# 2_MCU_schdoc.net
KiCad netlist of a schematic drawn in Altium Designer
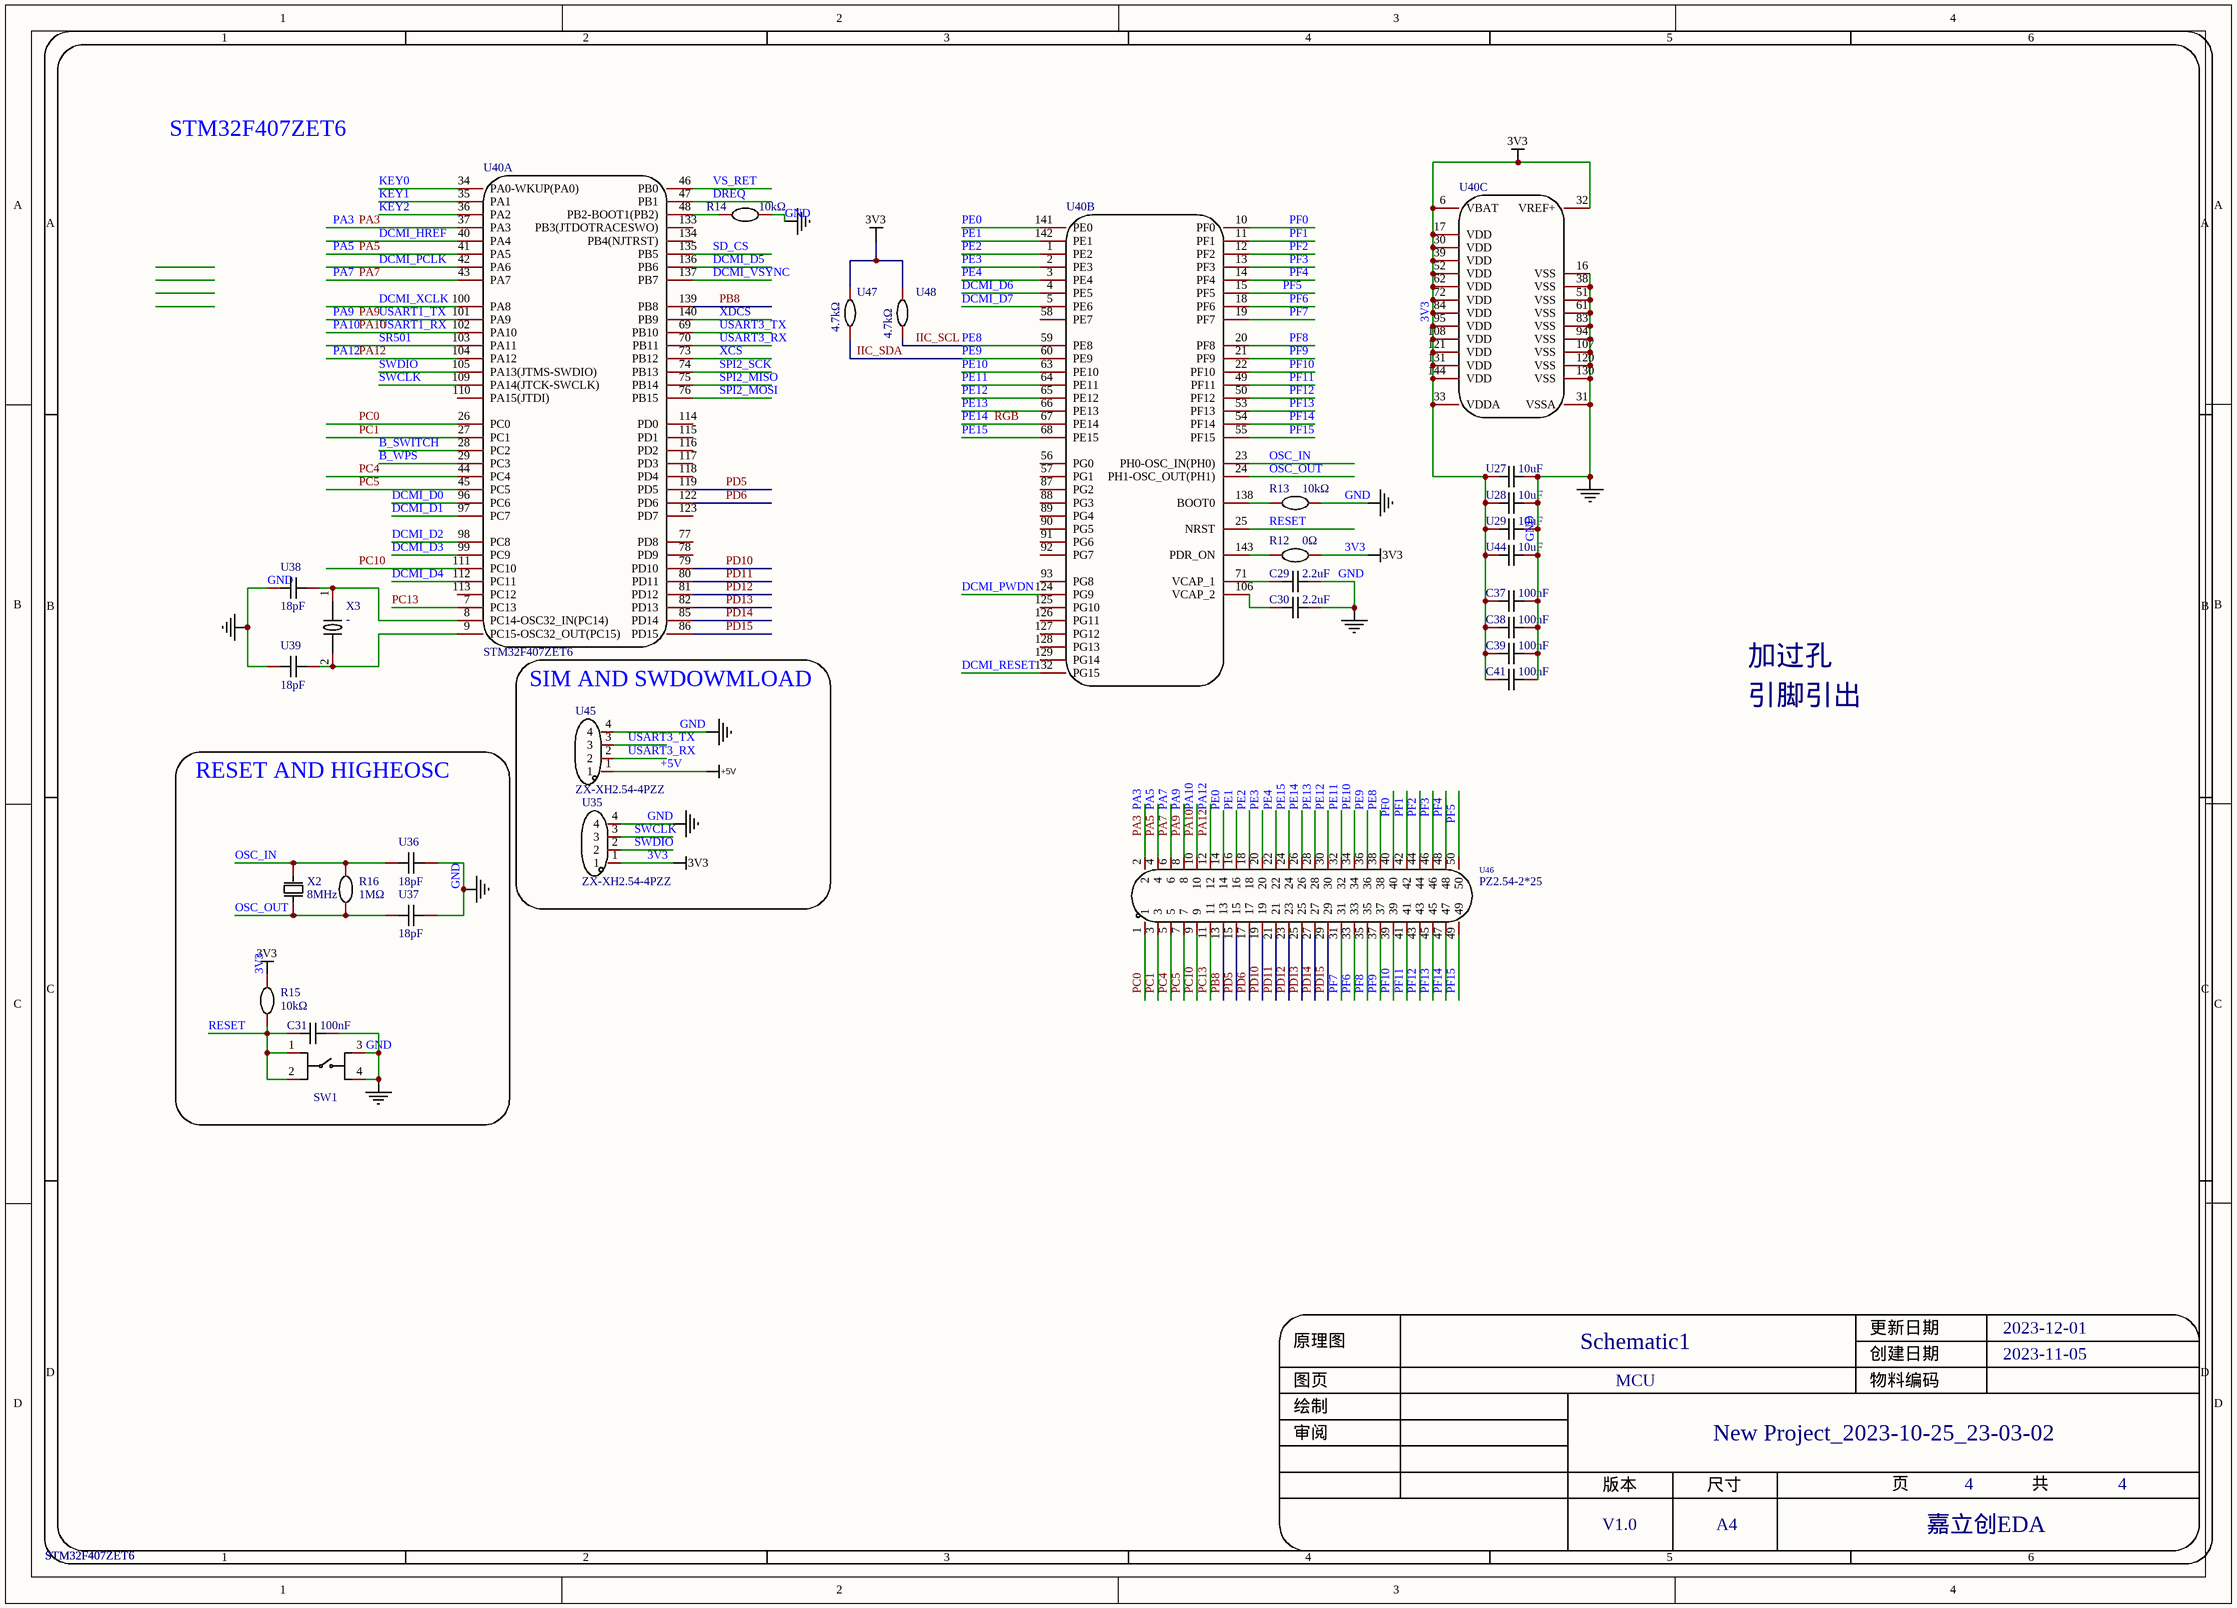
[diagram p0: 2_MCU.schdoc.schdoc]

(export (version "E")
  (design (tool "Eeschema 10.0.6"))
  (components
    (comp (ref "C29")
      (value "2.2uF")
      (footprint "C0603")
      (description "容值:2.2uF;精度:±10%;额定电压:10V;材质(温度系数):X6S;")
      (fields
        (field (name "NAME") "2.2uF")
        (field (name "MANUFACTURER") "TDK")
        (field (name "MANUFACTURER PART") "C1608X6S1A225K080AB")
      )
      (libsource (lib "altium-import") (part "root_0_C1608X6S1A225K080AB_"))
    )
    (comp (ref "C30")
      (value "2.2uF")
      (footprint "C0603")
      (description "容值:2.2uF;精度:±10%;额定电压:10V;材质(温度系数):X6S;")
      (fields
        (field (name "NAME") "2.2uF")
        (field (name "MANUFACTURER") "TDK")
        (field (name "MANUFACTURER PART") "C1608X6S1A225K080AB")
      )
      (libsource (lib "altium-import") (part "root_0_C1608X6S1A225K080AB_"))
    )
    (comp (ref "C31")
      (value "100nF")
      (footprint "C0603")
      (description "容值:100nF;精度:±20%;额定电压:50V;材质(温度系数):X8R;")
      (fields
        (field (name "NAME") "100nF")
        (field (name "MANUFACTURER") "TDK")
        (field (name "MANUFACTURER PART") "CGA3E3X8R1H104M080AE")
      )
      (libsource (lib "altium-import") (part "root_0_CGA3E3X8R1H104M080AE_"))
    )
    (comp (ref "C37")
      (value "100nF")
      (footprint "C0603")
      (description "容值:100nF;精度:±20%;额定电压:50V;材质(温度系数):X8R;")
      (fields
        (field (name "NAME") "100nF")
        (field (name "MANUFACTURER") "TDK")
        (field (name "MANUFACTURER PART") "CGA3E3X8R1H104M080AE")
      )
      (libsource (lib "altium-import") (part "root_0_CGA3E3X8R1H104M080AE_"))
    )
    (comp (ref "C38")
      (value "100nF")
      (footprint "C0603")
      (description "容值:100nF;精度:±20%;额定电压:50V;材质(温度系数):X8R;")
      (fields
        (field (name "NAME") "100nF")
        (field (name "MANUFACTURER") "TDK")
        (field (name "MANUFACTURER PART") "CGA3E3X8R1H104M080AE")
      )
      (libsource (lib "altium-import") (part "root_0_CGA3E3X8R1H104M080AE_"))
    )
    (comp (ref "C39")
      (value "100nF")
      (footprint "C0603")
      (description "容值:100nF;精度:±20%;额定电压:50V;材质(温度系数):X8R;")
      (fields
        (field (name "NAME") "100nF")
        (field (name "MANUFACTURER") "TDK")
        (field (name "MANUFACTURER PART") "CGA3E3X8R1H104M080AE")
      )
      (libsource (lib "altium-import") (part "root_0_CGA3E3X8R1H104M080AE_"))
    )
    (comp (ref "C41")
      (value "100nF")
      (footprint "C0603")
      (description "容值:100nF;精度:±20%;额定电压:50V;材质(温度系数):X8R;")
      (fields
        (field (name "NAME") "100nF")
        (field (name "MANUFACTURER") "TDK")
        (field (name "MANUFACTURER PART") "CGA3E3X8R1H104M080AE")
      )
      (libsource (lib "altium-import") (part "root_0_CGA3E3X8R1H104M080AE_"))
    )
    (comp (ref "R12")
      (value "0Ω")
      (footprint "R0603")
      (description "电阻类型:厚膜电阻;阻值:0Ω;精度:-;功率:100mW;")
      (fields
        (field (name "NAME") "0Ω")
        (field (name "MANUFACTURER") "YAGEO(国巨)")
        (field (name "MANUFACTURER PART") "RC0603JR-130RL")
      )
      (libsource (lib "altium-import") (part "root_0_RC0603JR-130RL_"))
    )
    (comp (ref "R13")
      (value "10kΩ")
      (footprint "R0603")
      (description "阻值:10kΩ;精度:±5%;")
      (fields
        (field (name "NAME") "10kΩ")
        (field (name "MANUFACTURER") "VO(翔胜)")
        (field (name "MANUFACTURER PART") "SCR0603J10K")
      )
      (libsource (lib "altium-import") (part "root_0_SCR0603J10K_"))
    )
    (comp (ref "R14")
      (value "10kΩ")
      (footprint "R0603")
      (description "阻值:10kΩ;精度:±5%;")
      (fields
        (field (name "NAME") "10kΩ")
        (field (name "MANUFACTURER") "VO(翔胜)")
        (field (name "MANUFACTURER PART") "SCR0603J10K")
      )
      (libsource (lib "altium-import") (part "root_0_SCR0603J10K_"))
    )
    (comp (ref "R15")
      (value "10kΩ")
      (footprint "R0603")
      (description "阻值:10kΩ;精度:±5%;")
      (fields
        (field (name "NAME") "10kΩ")
        (field (name "MANUFACTURER") "VO(翔胜)")
        (field (name "MANUFACTURER PART") "SCR0603J10K")
      )
      (libsource (lib "altium-import") (part "root_1_SCR0603J10K_"))
    )
    (comp (ref "R16")
      (value "1MΩ")
      (footprint "R0603")
      (description "电阻类型:厚膜电阻;阻值:1MΩ;精度:±5%;功率:100mW;")
      (fields
        (field (name "NAME") "1MΩ")
        (field (name "MANUFACTURER") "VISHAY(威世)")
        (field (name "MANUFACTURER PART") "CRCW06031M00JNEAC")
      )
      (libsource (lib "altium-import") (part "root_1_CRCW06031M00JNEAC_"))
    )
    (comp (ref "SW1")
      (value "K2-6639SP-C4SC-04")
      (footprint "KEY-SMD_4P-L6.0-W6.0-P3.90-LS10.0")
      (fields (field (name "MANUFACTURER") "韩国韩荣"))
      (libsource (lib "altium-import") (part "root_0_K2-6639SP-C4SC-04_"))
    )
    (comp (ref "U27")
      (value "10uF")
      (footprint "C0603")
      (description "容值:10uF;精度:±20%;额定电压:16V;材质(温度系数):JB;")
      (fields
        (field (name "NAME") "10uF")
        (field (name "MANUFACTURER") "TDK")
        (field (name "MANUFACTURER PART") "C1608JB1C106M080AB")
      )
      (libsource (lib "altium-import") (part "root_0_C1608JB1C106M080AB_"))
    )
    (comp (ref "U28")
      (value "10uF")
      (footprint "C0603")
      (description "容值:10uF;精度:±20%;额定电压:16V;材质(温度系数):JB;")
      (fields
        (field (name "NAME") "10uF")
        (field (name "MANUFACTURER") "TDK")
        (field (name "MANUFACTURER PART") "C1608JB1C106M080AB")
      )
      (libsource (lib "altium-import") (part "root_0_C1608JB1C106M080AB_"))
    )
    (comp (ref "U29")
      (value "10uF")
      (footprint "C0603")
      (description "容值:10uF;精度:±20%;额定电压:16V;材质(温度系数):JB;")
      (fields
        (field (name "NAME") "10uF")
        (field (name "MANUFACTURER") "TDK")
        (field (name "MANUFACTURER PART") "C1608JB1C106M080AB")
      )
      (libsource (lib "altium-import") (part "root_0_C1608JB1C106M080AB_"))
    )
    (comp (ref "U35")
      (value "ZX-XH2.54-4PZZ")
      (footprint "CONN-TH_4P-P2.50_4PIN")
      (fields (field (name "NAME") "ZX-XH2.54-4PZZ") (field (name "MANUFACTURER") "Megastar(兆星)"))
      (libsource (lib "altium-import") (part "root_2_ZX-XH2.54-4PZZ_"))
    )
    (comp (ref "U36")
      (value "18pF")
      (footprint "C0603")
      (description "容值:18pF;精度:±5%;额定电压:100V;材质(温度系数):CH;")
      (fields
        (field (name "NAME") "18pF")
        (field (name "MANUFACTURER") "TDK")
        (field (name "MANUFACTURER PART") "C1608CH2A180J080AA")
      )
      (libsource (lib "altium-import") (part "root_0_C1608CH2A180J080AA_"))
    )
    (comp (ref "U37")
      (value "18pF")
      (footprint "C0603")
      (description "容值:18pF;精度:±5%;额定电压:100V;材质(温度系数):CH;")
      (fields
        (field (name "NAME") "18pF")
        (field (name "MANUFACTURER") "TDK")
        (field (name "MANUFACTURER PART") "C1608CH2A180J080AA")
      )
      (libsource (lib "altium-import") (part "root_0_C1608CH2A180J080AA_"))
    )
    (comp (ref "U38")
      (value "18pF")
      (footprint "C0603")
      (description "容值:18pF;精度:±5%;额定电压:100V;材质(温度系数):CH;")
      (fields
        (field (name "NAME") "18pF")
        (field (name "MANUFACTURER") "TDK")
        (field (name "MANUFACTURER PART") "C1608CH2A180J080AA")
      )
      (libsource (lib "altium-import") (part "root_0_C1608CH2A180J080AA_"))
    )
    (comp (ref "U39")
      (value "18pF")
      (footprint "C0603")
      (description "容值:18pF;精度:±5%;额定电压:100V;材质(温度系数):CH;")
      (fields
        (field (name "NAME") "18pF")
        (field (name "MANUFACTURER") "TDK")
        (field (name "MANUFACTURER PART") "C1608CH2A180J080AA")
      )
      (libsource (lib "altium-import") (part "root_0_C1608CH2A180J080AA_"))
    )
    (comp (ref "U40")
      (value "STM32F407ZET6")
      (footprint "LQFP-144_L20.0-W20.0-P0.50-LS22.0-BL")
      (fields (field (name "NAME") "STM32F407ZET6") (field (name "MANUFACTURER") "ST(意法半导体)"))
      (libsource (lib "altium-import") (part "root_0_STM32F407ZET6_"))
    )
    (comp (ref "U44")
      (value "10uF")
      (footprint "C0603")
      (description "容值:10uF;精度:±20%;额定电压:16V;材质(温度系数):JB;")
      (fields
        (field (name "NAME") "10uF")
        (field (name "MANUFACTURER") "TDK")
        (field (name "MANUFACTURER PART") "C1608JB1C106M080AB")
      )
      (libsource (lib "altium-import") (part "root_0_C1608JB1C106M080AB_"))
    )
    (comp (ref "U45")
      (value "ZX-XH2.54-4PZZ")
      (footprint "CONN-TH_4P-P2.50_4PIN")
      (fields (field (name "NAME") "ZX-XH2.54-4PZZ") (field (name "MANUFACTURER") "Megastar(兆星)"))
      (libsource (lib "altium-import") (part "root_2_ZX-XH2.54-4PZZ_"))
    )
    (comp (ref "U46")
      (value "PZ2.54-2*25")
      (footprint "HDR-TH_50P-P2.54-V-M-R2-C25-S2.54")
      (fields (field (name "NAME") "PZ2.54-2*25") (field (name "MANUFACTURER") "ZHOURI(洲日)"))
      (libsource (lib "altium-import") (part "root_1_PZ2.54-2*25_"))
    )
    (comp (ref "U47")
      (value "4.7kΩ")
      (footprint "R0603")
      (description "电阻类型:薄膜电阻;阻值:4.7kΩ;精度:±1%;功率:100mW;")
      (fields
        (field (name "NAME") "4.7kΩ")
        (field (name "MANUFACTURER") "Viking(光颉)")
        (field (name "MANUFACTURER PART") "AR03FTDX4701A")
      )
      (libsource (lib "altium-import") (part "root_3_AR03FTDX4701A_"))
    )
    (comp (ref "U48")
      (value "4.7kΩ")
      (footprint "R0603")
      (description "电阻类型:薄膜电阻;阻值:4.7kΩ;精度:±1%;功率:100mW;")
      (fields
        (field (name "NAME") "4.7kΩ")
        (field (name "MANUFACTURER") "Viking(光颉)")
        (field (name "MANUFACTURER PART") "AR03FTDX4701A")
      )
      (libsource (lib "altium-import") (part "root_3_AR03FTDX4701A_"))
    )
    (comp (ref "X2")
      (value "8MHz")
      (footprint "OSC-SMD_L5.0-W3.2")
      (description "频率:8MHz;频率公差:±30ppm;负载电容:20pF;")
      (fields
        (field (name "NAME") "8MHz")
        (field (name "MANUFACTURER") "TAE(雅晶鑫)")
        (field (name "MANUFACTURER PART") "TAXM8M2QLFCDT1T")
      )
      (libsource (lib "altium-import") (part "root_1_TAXM8M2QLFCDT1T_"))
    )
    (comp (ref "X3")
      (value "-")
      (footprint "OSC-SMD_2P-L1.6-W1.0")
      (description "频率:-;负载电容:-;")
      (fields
        (field (name "NAME") "-")
        (field (name "MANUFACTURER") "RIVER(大河)")
        (field (name "MANUFACTURER PART") "TFX-04-32.768K")
      )
      (libsource (lib "altium-import") (part "root_3_TFX-04-32.768K_"))
    )
  )
  (nets
    (net (code "1") (name "+5V") (class "Default")
      (node (ref "U45") (pin "1") (pinfunction "1_1") (pintype "passive"))
    )
    (net (code "2") (name "/B_SWITCH") (class "Default")
      (node (ref "U40") (pin "28") (pinfunction "PC2_28") (pintype "passive"))
    )
    (net (code "3") (name "/B_WPS") (class "Default")
      (node (ref "U40") (pin "29") (pinfunction "PC3_29") (pintype "passive"))
    )
    (net (code "4") (name "/DCMI_D0") (class "Default")
      (node (ref "U40") (pin "96") (pinfunction "PC6_96") (pintype "passive"))
    )
    (net (code "5") (name "/DCMI_D1") (class "Default")
      (node (ref "U40") (pin "97") (pinfunction "PC7_97") (pintype "passive"))
    )
    (net (code "6") (name "/DCMI_D2") (class "Default")
      (node (ref "U40") (pin "98") (pinfunction "PC8_98") (pintype "passive"))
    )
    (net (code "7") (name "/DCMI_D3") (class "Default")
      (node (ref "U40") (pin "99") (pinfunction "PC9_99") (pintype "passive"))
    )
    (net (code "8") (name "/DCMI_D4") (class "Default")
      (node (ref "U40") (pin "112") (pinfunction "PC11_112") (pintype "passive"))
    )
    (net (code "9") (name "/DCMI_D5") (class "Default")
      (node (ref "U40") (pin "136") (pinfunction "PB6_136") (pintype "passive"))
    )
    (net (code "10") (name "/DCMI_D6") (class "Default")
      (node (ref "U40") (pin "4") (pinfunction "PE5_4") (pintype "passive"))
    )
    (net (code "11") (name "/DCMI_D7") (class "Default")
      (node (ref "U40") (pin "5") (pinfunction "PE6_5") (pintype "passive"))
    )
    (net (code "12") (name "/DCMI_HREF") (class "Default")
      (node (ref "U40") (pin "40") (pinfunction "PA4_40") (pintype "passive"))
    )
    (net (code "13") (name "/DCMI_PCLK") (class "Default")
      (node (ref "U40") (pin "42") (pinfunction "PA6_42") (pintype "passive"))
    )
    (net (code "14") (name "/DCMI_PWDN") (class "Default")
      (node (ref "U40") (pin "124") (pinfunction "PG9_124") (pintype "passive"))
    )
    (net (code "15") (name "/DCMI_RESET") (class "Default")
      (node (ref "U40") (pin "132") (pinfunction "PG15_132") (pintype "passive"))
    )
    (net (code "16") (name "/DCMI_VSYNC") (class "Default")
      (node (ref "U40") (pin "137") (pinfunction "PB7_137") (pintype "passive"))
    )
    (net (code "17") (name "/DCMI_XCLK") (class "Default")
      (node (ref "U40") (pin "100") (pinfunction "PA8_100") (pintype "passive"))
    )
    (net (code "18") (name "/DREQ") (class "Default")
      (node (ref "U40") (pin "47") (pinfunction "PB1_47") (pintype "passive"))
    )
    (net (code "19") (name "/GND") (class "Default")
      (node (ref "C29") (pin "2") (pinfunction "2_2") (pintype "passive"))
      (node (ref "C30") (pin "2") (pinfunction "2_2") (pintype "passive"))
      (node (ref "C31") (pin "2") (pinfunction "2_2") (pintype "passive"))
      (node (ref "C37") (pin "2") (pinfunction "2_2") (pintype "passive"))
      (node (ref "C38") (pin "2") (pinfunction "2_2") (pintype "passive"))
      (node (ref "C39") (pin "2") (pinfunction "2_2") (pintype "passive"))
      (node (ref "C41") (pin "2") (pinfunction "2_2") (pintype "passive"))
      (node (ref "R13") (pin "2") (pinfunction "2_2") (pintype "passive"))
      (node (ref "R14") (pin "2") (pinfunction "2_2") (pintype "passive"))
      (node (ref "SW1") (pin "3") (pinfunction "3_3") (pintype "passive"))
      (node (ref "SW1") (pin "4") (pinfunction "4_4") (pintype "passive"))
      (node (ref "U27") (pin "2") (pinfunction "2_2") (pintype "passive"))
      (node (ref "U28") (pin "2") (pinfunction "2_2") (pintype "passive"))
      (node (ref "U29") (pin "2") (pinfunction "2_2") (pintype "passive"))
      (node (ref "U35") (pin "4") (pinfunction "4_4") (pintype "passive"))
      (node (ref "U36") (pin "2") (pinfunction "2_2") (pintype "passive"))
      (node (ref "U37") (pin "2") (pinfunction "2_2") (pintype "passive"))
      (node (ref "U38") (pin "1") (pinfunction "1_1") (pintype "passive"))
      (node (ref "U39") (pin "1") (pinfunction "1_1") (pintype "passive"))
      (node (ref "U40") (pin "107") (pinfunction "VSS_107") (pintype "passive"))
      (node (ref "U40") (pin "120") (pinfunction "VSS_120") (pintype "passive"))
      (node (ref "U40") (pin "130") (pinfunction "VSS_130") (pintype "passive"))
      (node (ref "U40") (pin "16") (pinfunction "VSS_16") (pintype "passive"))
      (node (ref "U40") (pin "31") (pinfunction "VSSA_31") (pintype "passive"))
      (node (ref "U40") (pin "38") (pinfunction "VSS_38") (pintype "passive"))
      (node (ref "U40") (pin "51") (pinfunction "VSS_51") (pintype "passive"))
      (node (ref "U40") (pin "61") (pinfunction "VSS_61") (pintype "passive"))
      (node (ref "U40") (pin "83") (pinfunction "VSS_83") (pintype "passive"))
      (node (ref "U40") (pin "94") (pinfunction "VSS_94") (pintype "passive"))
      (node (ref "U44") (pin "2") (pinfunction "2_2") (pintype "passive"))
      (node (ref "U45") (pin "4") (pinfunction "4_4") (pintype "passive"))
    )
    (net (code "20") (name "/IIC_SCL") (class "Default")
      (node (ref "U40") (pin "59") (pinfunction "PE8_59") (pintype "passive"))
      (node (ref "U46") (pin "38") (pinfunction "38_38") (pintype "passive"))
      (node (ref "U48") (pin "2") (pinfunction "2_2") (pintype "passive"))
    )
    (net (code "21") (name "/IIC_SDA") (class "Default")
      (node (ref "U40") (pin "60") (pinfunction "PE9_60") (pintype "passive"))
      (node (ref "U46") (pin "36") (pinfunction "36_36") (pintype "passive"))
      (node (ref "U47") (pin "2") (pinfunction "2_2") (pintype "passive"))
    )
    (net (code "22") (name "/KEY0") (class "Default")
      (node (ref "U40") (pin "34") (pinfunction "PA0-WKUP(PA0)_34") (pintype "passive"))
    )
    (net (code "23") (name "/KEY1") (class "Default")
      (node (ref "U40") (pin "35") (pinfunction "PA1_35") (pintype "passive"))
    )
    (net (code "24") (name "/KEY2") (class "Default")
      (node (ref "U40") (pin "36") (pinfunction "PA2_36") (pintype "passive"))
    )
    (net (code "25") (name "/OSC_IN") (class "Default")
      (node (ref "R16") (pin "2") (pinfunction "2_2") (pintype "passive"))
      (node (ref "U36") (pin "1") (pinfunction "1_1") (pintype "passive"))
      (node (ref "U40") (pin "23") (pinfunction "PH0-OSC_IN(PH0)_23") (pintype "passive"))
      (node (ref "X2") (pin "2") (pinfunction "OSC2_2") (pintype "passive"))
    )
    (net (code "26") (name "/OSC_OUT") (class "Default")
      (node (ref "R16") (pin "1") (pinfunction "1_1") (pintype "passive"))
      (node (ref "U37") (pin "1") (pinfunction "1_1") (pintype "passive"))
      (node (ref "U40") (pin "24") (pinfunction "PH1-OSC_OUT(PH1)_24") (pintype "passive"))
      (node (ref "X2") (pin "1") (pinfunction "OSC1_1") (pintype "passive"))
    )
    (net (code "27") (name "/PA3") (class "Default")
      (node (ref "U40") (pin "37") (pinfunction "PA3_37") (pintype "passive"))
      (node (ref "U46") (pin "2") (pinfunction "2_2") (pintype "passive"))
    )
    (net (code "28") (name "/PA5") (class "Default")
      (node (ref "U40") (pin "41") (pinfunction "PA5_41") (pintype "passive"))
      (node (ref "U46") (pin "4") (pinfunction "4_4") (pintype "passive"))
    )
    (net (code "29") (name "/PA7") (class "Default")
      (node (ref "U40") (pin "43") (pinfunction "PA7_43") (pintype "passive"))
      (node (ref "U46") (pin "6") (pinfunction "6_6") (pintype "passive"))
    )
    (net (code "30") (name "/PA9") (class "Default")
      (node (ref "U40") (pin "101") (pinfunction "PA9_101") (pintype "passive"))
      (node (ref "U46") (pin "8") (pinfunction "8_8") (pintype "passive"))
    )
    (net (code "31") (name "/PA10") (class "Default")
      (node (ref "U40") (pin "102") (pinfunction "PA10_102") (pintype "passive"))
      (node (ref "U46") (pin "10") (pinfunction "10_10") (pintype "passive"))
    )
    (net (code "32") (name "/PA12") (class "Default")
      (node (ref "U40") (pin "104") (pinfunction "PA12_104") (pintype "passive"))
      (node (ref "U46") (pin "12") (pinfunction "12_12") (pintype "passive"))
    )
    (net (code "33") (name "/PB8") (class "Default")
      (node (ref "U40") (pin "139") (pinfunction "PB8_139") (pintype "passive"))
      (node (ref "U46") (pin "13") (pinfunction "13_13") (pintype "passive"))
    )
    (net (code "34") (name "/PC0") (class "Default")
      (node (ref "U40") (pin "26") (pinfunction "PC0_26") (pintype "passive"))
      (node (ref "U46") (pin "1") (pinfunction "1_1") (pintype "passive"))
    )
    (net (code "35") (name "/PC1") (class "Default")
      (node (ref "U40") (pin "27") (pinfunction "PC1_27") (pintype "passive"))
      (node (ref "U46") (pin "3") (pinfunction "3_3") (pintype "passive"))
    )
    (net (code "36") (name "/PC4") (class "Default")
      (node (ref "U40") (pin "44") (pinfunction "PC4_44") (pintype "passive"))
      (node (ref "U46") (pin "5") (pinfunction "5_5") (pintype "passive"))
    )
    (net (code "37") (name "/PC5") (class "Default")
      (node (ref "U40") (pin "45") (pinfunction "PC5_45") (pintype "passive"))
      (node (ref "U46") (pin "7") (pinfunction "7_7") (pintype "passive"))
    )
    (net (code "38") (name "/PC10") (class "Default")
      (node (ref "U40") (pin "111") (pinfunction "PC10_111") (pintype "passive"))
      (node (ref "U46") (pin "9") (pinfunction "9_9") (pintype "passive"))
    )
    (net (code "39") (name "/PC13") (class "Default")
      (node (ref "U40") (pin "7") (pinfunction "PC13_7") (pintype "passive"))
      (node (ref "U46") (pin "11") (pinfunction "11_11") (pintype "passive"))
    )
    (net (code "40") (name "/PD5") (class "Default")
      (node (ref "U40") (pin "119") (pinfunction "PD5_119") (pintype "passive"))
      (node (ref "U46") (pin "15") (pinfunction "15_15") (pintype "passive"))
    )
    (net (code "41") (name "/PD6") (class "Default")
      (node (ref "U40") (pin "122") (pinfunction "PD6_122") (pintype "passive"))
      (node (ref "U46") (pin "17") (pinfunction "17_17") (pintype "passive"))
    )
    (net (code "42") (name "/PD10") (class "Default")
      (node (ref "U40") (pin "79") (pinfunction "PD10_79") (pintype "passive"))
      (node (ref "U46") (pin "19") (pinfunction "19_19") (pintype "passive"))
    )
    (net (code "43") (name "/PD11") (class "Default")
      (node (ref "U40") (pin "80") (pinfunction "PD11_80") (pintype "passive"))
      (node (ref "U46") (pin "21") (pinfunction "21_21") (pintype "passive"))
    )
    (net (code "44") (name "/PD12") (class "Default")
      (node (ref "U40") (pin "81") (pinfunction "PD12_81") (pintype "passive"))
      (node (ref "U46") (pin "23") (pinfunction "23_23") (pintype "passive"))
    )
    (net (code "45") (name "/PD13") (class "Default")
      (node (ref "U40") (pin "82") (pinfunction "PD13_82") (pintype "passive"))
      (node (ref "U46") (pin "25") (pinfunction "25_25") (pintype "passive"))
    )
    (net (code "46") (name "/PD14") (class "Default")
      (node (ref "U40") (pin "85") (pinfunction "PD14_85") (pintype "passive"))
      (node (ref "U46") (pin "27") (pinfunction "27_27") (pintype "passive"))
    )
    (net (code "47") (name "/PD15") (class "Default")
      (node (ref "U40") (pin "86") (pinfunction "PD15_86") (pintype "passive"))
      (node (ref "U46") (pin "29") (pinfunction "29_29") (pintype "passive"))
    )
    (net (code "48") (name "/PE0") (class "Default")
      (node (ref "U40") (pin "141") (pinfunction "PE0_141") (pintype "passive"))
      (node (ref "U46") (pin "14") (pinfunction "14_14") (pintype "passive"))
    )
    (net (code "49") (name "/PE1") (class "Default")
      (node (ref "U40") (pin "142") (pinfunction "PE1_142") (pintype "passive"))
      (node (ref "U46") (pin "16") (pinfunction "16_16") (pintype "passive"))
    )
    (net (code "50") (name "/PE2") (class "Default")
      (node (ref "U40") (pin "1") (pinfunction "PE2_1") (pintype "passive"))
      (node (ref "U46") (pin "18") (pinfunction "18_18") (pintype "passive"))
    )
    (net (code "51") (name "/PE3") (class "Default")
      (node (ref "U40") (pin "2") (pinfunction "PE3_2") (pintype "passive"))
      (node (ref "U46") (pin "20") (pinfunction "20_20") (pintype "passive"))
    )
    (net (code "52") (name "/PE4") (class "Default")
      (node (ref "U40") (pin "3") (pinfunction "PE4_3") (pintype "passive"))
      (node (ref "U46") (pin "22") (pinfunction "22_22") (pintype "passive"))
    )
    (net (code "53") (name "/PE10") (class "Default")
      (node (ref "U40") (pin "63") (pinfunction "PE10_63") (pintype "passive"))
      (node (ref "U46") (pin "34") (pinfunction "34_34") (pintype "passive"))
    )
    (net (code "54") (name "/PE11") (class "Default")
      (node (ref "U40") (pin "64") (pinfunction "PE11_64") (pintype "passive"))
      (node (ref "U46") (pin "32") (pinfunction "32_32") (pintype "passive"))
    )
    (net (code "55") (name "/PE12") (class "Default")
      (node (ref "U40") (pin "65") (pinfunction "PE12_65") (pintype "passive"))
      (node (ref "U46") (pin "30") (pinfunction "30_30") (pintype "passive"))
    )
    (net (code "56") (name "/PE13") (class "Default")
      (node (ref "U40") (pin "66") (pinfunction "PE13_66") (pintype "passive"))
      (node (ref "U46") (pin "28") (pinfunction "28_28") (pintype "passive"))
    )
    (net (code "57") (name "/PE14") (class "Default")
      (node (ref "U40") (pin "67") (pinfunction "PE14_67") (pintype "passive"))
      (node (ref "U46") (pin "26") (pinfunction "26_26") (pintype "passive"))
    )
    (net (code "58") (name "/PE15") (class "Default")
      (node (ref "U40") (pin "68") (pinfunction "PE15_68") (pintype "passive"))
      (node (ref "U46") (pin "24") (pinfunction "24_24") (pintype "passive"))
    )
    (net (code "59") (name "/PF0") (class "Default")
      (node (ref "U40") (pin "10") (pinfunction "PF0_10") (pintype "passive"))
      (node (ref "U46") (pin "40") (pinfunction "40_40") (pintype "passive"))
    )
    (net (code "60") (name "/PF1") (class "Default")
      (node (ref "U40") (pin "11") (pinfunction "PF1_11") (pintype "passive"))
      (node (ref "U46") (pin "42") (pinfunction "42_42") (pintype "passive"))
    )
    (net (code "61") (name "/PF2") (class "Default")
      (node (ref "U40") (pin "12") (pinfunction "PF2_12") (pintype "passive"))
      (node (ref "U46") (pin "44") (pinfunction "44_44") (pintype "passive"))
    )
    (net (code "62") (name "/PF3") (class "Default")
      (node (ref "U40") (pin "13") (pinfunction "PF3_13") (pintype "passive"))
      (node (ref "U46") (pin "46") (pinfunction "46_46") (pintype "passive"))
    )
    (net (code "63") (name "/PF4") (class "Default")
      (node (ref "U40") (pin "14") (pinfunction "PF4_14") (pintype "passive"))
      (node (ref "U46") (pin "48") (pinfunction "48_48") (pintype "passive"))
    )
    (net (code "64") (name "/PF5") (class "Default")
      (node (ref "U40") (pin "15") (pinfunction "PF5_15") (pintype "passive"))
      (node (ref "U46") (pin "50") (pinfunction "50_50") (pintype "passive"))
    )
    (net (code "65") (name "/PF6") (class "Default")
      (node (ref "U40") (pin "18") (pinfunction "PF6_18") (pintype "passive"))
      (node (ref "U46") (pin "33") (pinfunction "33_33") (pintype "passive"))
    )
    (net (code "66") (name "/PF7") (class "Default")
      (node (ref "U40") (pin "19") (pinfunction "PF7_19") (pintype "passive"))
      (node (ref "U46") (pin "31") (pinfunction "31_31") (pintype "passive"))
    )
    (net (code "67") (name "/PF8") (class "Default")
      (node (ref "U40") (pin "20") (pinfunction "PF8_20") (pintype "passive"))
      (node (ref "U46") (pin "35") (pinfunction "35_35") (pintype "passive"))
    )
    (net (code "68") (name "/PF9") (class "Default")
      (node (ref "U40") (pin "21") (pinfunction "PF9_21") (pintype "passive"))
      (node (ref "U46") (pin "37") (pinfunction "37_37") (pintype "passive"))
    )
    (net (code "69") (name "/PF10") (class "Default")
      (node (ref "U40") (pin "22") (pinfunction "PF10_22") (pintype "passive"))
      (node (ref "U46") (pin "39") (pinfunction "39_39") (pintype "passive"))
    )
    (net (code "70") (name "/PF11") (class "Default")
      (node (ref "U40") (pin "49") (pinfunction "PF11_49") (pintype "passive"))
      (node (ref "U46") (pin "41") (pinfunction "41_41") (pintype "passive"))
    )
    (net (code "71") (name "/PF12") (class "Default")
      (node (ref "U40") (pin "50") (pinfunction "PF12_50") (pintype "passive"))
      (node (ref "U46") (pin "43") (pinfunction "43_43") (pintype "passive"))
    )
    (net (code "72") (name "/PF13") (class "Default")
      (node (ref "U40") (pin "53") (pinfunction "PF13_53") (pintype "passive"))
      (node (ref "U46") (pin "45") (pinfunction "45_45") (pintype "passive"))
    )
    (net (code "73") (name "/PF14") (class "Default")
      (node (ref "U40") (pin "54") (pinfunction "PF14_54") (pintype "passive"))
      (node (ref "U46") (pin "47") (pinfunction "47_47") (pintype "passive"))
    )
    (net (code "74") (name "/PF15") (class "Default")
      (node (ref "U40") (pin "55") (pinfunction "PF15_55") (pintype "passive"))
      (node (ref "U46") (pin "49") (pinfunction "49_49") (pintype "passive"))
    )
    (net (code "75") (name "/RESET") (class "Default")
      (node (ref "C31") (pin "1") (pinfunction "1_1") (pintype "passive"))
      (node (ref "R15") (pin "1") (pinfunction "1_1") (pintype "passive"))
      (node (ref "SW1") (pin "1") (pinfunction "1_1") (pintype "passive"))
      (node (ref "SW1") (pin "2") (pinfunction "2_2") (pintype "passive"))
      (node (ref "U40") (pin "25") (pinfunction "NRST_25") (pintype "passive"))
    )
    (net (code "76") (name "/SD_CS") (class "Default")
      (node (ref "U40") (pin "135") (pinfunction "PB5_135") (pintype "passive"))
    )
    (net (code "77") (name "/SPI2_MISO") (class "Default")
      (node (ref "U40") (pin "75") (pinfunction "PB14_75") (pintype "passive"))
    )
    (net (code "78") (name "/SPI2_MOSI") (class "Default")
      (node (ref "U40") (pin "76") (pinfunction "PB15_76") (pintype "passive"))
    )
    (net (code "79") (name "/SPI2_SCK") (class "Default")
      (node (ref "U40") (pin "74") (pinfunction "PB13_74") (pintype "passive"))
    )
    (net (code "80") (name "/SR501") (class "Default")
      (node (ref "U40") (pin "103") (pinfunction "PA11_103") (pintype "passive"))
    )
    (net (code "81") (name "/SWCLK") (class "Default")
      (node (ref "U35") (pin "3") (pinfunction "3_3") (pintype "passive"))
      (node (ref "U40") (pin "109") (pinfunction "PA14(JTCK-SWCLK)_109") (pintype "passive"))
    )
    (net (code "82") (name "/SWDIO") (class "Default")
      (node (ref "U35") (pin "2") (pinfunction "2_2") (pintype "passive"))
      (node (ref "U40") (pin "105") (pinfunction "PA13(JTMS-SWDIO)_105") (pintype "passive"))
    )
    (net (code "83") (name "/USART3_RX") (class "Default")
      (node (ref "U40") (pin "70") (pinfunction "PB11_70") (pintype "passive"))
      (node (ref "U45") (pin "2") (pinfunction "2_2") (pintype "passive"))
    )
    (net (code "84") (name "/USART3_TX") (class "Default")
      (node (ref "U40") (pin "69") (pinfunction "PB10_69") (pintype "passive"))
      (node (ref "U45") (pin "3") (pinfunction "3_3") (pintype "passive"))
    )
    (net (code "85") (name "/VS_RET") (class "Default")
      (node (ref "U40") (pin "46") (pinfunction "PB0_46") (pintype "passive"))
    )
    (net (code "86") (name "/XCS") (class "Default")
      (node (ref "U40") (pin "73") (pinfunction "PB12_73") (pintype "passive"))
    )
    (net (code "87") (name "/XDCS") (class "Default")
      (node (ref "U40") (pin "140") (pinfunction "PB9_140") (pintype "passive"))
    )
    (net (code "88") (name "3V3") (class "Default")
      (node (ref "C37") (pin "1") (pinfunction "1_1") (pintype "passive"))
      (node (ref "C38") (pin "1") (pinfunction "1_1") (pintype "passive"))
      (node (ref "C39") (pin "1") (pinfunction "1_1") (pintype "passive"))
      (node (ref "C41") (pin "1") (pinfunction "1_1") (pintype "passive"))
      (node (ref "R12") (pin "2") (pinfunction "2_2") (pintype "passive"))
      (node (ref "R15") (pin "2") (pinfunction "2_2") (pintype "passive"))
      (node (ref "U27") (pin "1") (pinfunction "1_1") (pintype "passive"))
      (node (ref "U28") (pin "1") (pinfunction "1_1") (pintype "passive"))
      (node (ref "U29") (pin "1") (pinfunction "1_1") (pintype "passive"))
      (node (ref "U35") (pin "1") (pinfunction "1_1") (pintype "passive"))
      (node (ref "U40") (pin "108") (pinfunction "VDD_108") (pintype "passive"))
      (node (ref "U40") (pin "121") (pinfunction "VDD_121") (pintype "passive"))
      (node (ref "U40") (pin "131") (pinfunction "VDD_131") (pintype "passive"))
      (node (ref "U40") (pin "144") (pinfunction "VDD_144") (pintype "passive"))
      (node (ref "U40") (pin "17") (pinfunction "VDD_17") (pintype "passive"))
      (node (ref "U40") (pin "30") (pinfunction "VDD_30") (pintype "passive"))
      (node (ref "U40") (pin "32") (pinfunction "VREF+_32") (pintype "passive"))
      (node (ref "U40") (pin "33") (pinfunction "VDDA_33") (pintype "passive"))
      (node (ref "U40") (pin "39") (pinfunction "VDD_39") (pintype "passive"))
      (node (ref "U40") (pin "52") (pinfunction "VDD_52") (pintype "passive"))
      (node (ref "U40") (pin "6") (pinfunction "VBAT_6") (pintype "passive"))
      (node (ref "U40") (pin "62") (pinfunction "VDD_62") (pintype "passive"))
      (node (ref "U40") (pin "72") (pinfunction "VDD_72") (pintype "passive"))
      (node (ref "U40") (pin "84") (pinfunction "VDD_84") (pintype "passive"))
      (node (ref "U40") (pin "95") (pinfunction "VDD_95") (pintype "passive"))
      (node (ref "U44") (pin "1") (pinfunction "1_1") (pintype "passive"))
      (node (ref "U47") (pin "1") (pinfunction "1_1") (pintype "passive"))
      (node (ref "U48") (pin "1") (pinfunction "1_1") (pintype "passive"))
    )
    (net (code "89") (name "Net-(U40A-PB2-BOOT1(PB2))") (class "Default")
      (node (ref "R14") (pin "1") (pinfunction "1_1") (pintype "passive"))
      (node (ref "U40") (pin "48") (pinfunction "PB2-BOOT1(PB2)_48") (pintype "passive"))
    )
    (net (code "90") (name "Net-(U40A-PC14-OSC32_IN(PC14))") (class "Default")
      (node (ref "U38") (pin "2") (pinfunction "2_2") (pintype "passive"))
      (node (ref "U40") (pin "8") (pinfunction "PC14-OSC32_IN(PC14)_8") (pintype "passive"))
      (node (ref "X3") (pin "1") (pinfunction "1_1") (pintype "passive"))
    )
    (net (code "91") (name "Net-(U40A-PC15-OSC32_OUT(PC15))") (class "Default")
      (node (ref "U39") (pin "2") (pinfunction "2_2") (pintype "passive"))
      (node (ref "U40") (pin "9") (pinfunction "PC15-OSC32_OUT(PC15)_9") (pintype "passive"))
      (node (ref "X3") (pin "2") (pinfunction "2_2") (pintype "passive"))
    )
    (net (code "92") (name "Net-(U40B-BOOT0)") (class "Default")
      (node (ref "R13") (pin "1") (pinfunction "1_1") (pintype "passive"))
      (node (ref "U40") (pin "138") (pinfunction "BOOT0_138") (pintype "passive"))
    )
    (net (code "93") (name "Net-(U40B-PDR_ON)") (class "Default")
      (node (ref "R12") (pin "1") (pinfunction "1_1") (pintype "passive"))
      (node (ref "U40") (pin "143") (pinfunction "PDR_ON_143") (pintype "passive"))
    )
    (net (code "94") (name "Net-(U40B-VCAP_1)") (class "Default")
      (node (ref "C29") (pin "1") (pinfunction "1_1") (pintype "passive"))
      (node (ref "U40") (pin "71") (pinfunction "VCAP_1_71") (pintype "passive"))
    )
    (net (code "95") (name "Net-(U40B-VCAP_2)") (class "Default")
      (node (ref "C30") (pin "1") (pinfunction "1_1") (pintype "passive"))
      (node (ref "U40") (pin "106") (pinfunction "VCAP_2_106") (pintype "passive"))
    )
    (net (code "96") (name "unconnected-(U40A-PA15(JTDI)-Pad110)") (class "Default")
      (node (ref "U40") (pin "110") (pinfunction "PA15(JTDI)_110") (pintype "passive"))
    )
    (net (code "97") (name "unconnected-(U40A-PB3(JTDOTRACESWO)-Pad133)") (class "Default")
      (node (ref "U40") (pin "133") (pinfunction "PB3(JTDOTRACESWO)_133") (pintype "passive"))
    )
    (net (code "98") (name "unconnected-(U40A-PB4(NJTRST)-Pad134)") (class "Default")
      (node (ref "U40") (pin "134") (pinfunction "PB4(NJTRST)_134") (pintype "passive"))
    )
    (net (code "99") (name "unconnected-(U40A-PC12-Pad113)") (class "Default")
      (node (ref "U40") (pin "113") (pinfunction "PC12_113") (pintype "passive"))
    )
    (net (code "100") (name "unconnected-(U40A-PD0-Pad114)") (class "Default")
      (node (ref "U40") (pin "114") (pinfunction "PD0_114") (pintype "passive"))
    )
    (net (code "101") (name "unconnected-(U40A-PD1-Pad115)") (class "Default")
      (node (ref "U40") (pin "115") (pinfunction "PD1_115") (pintype "passive"))
    )
    (net (code "102") (name "unconnected-(U40A-PD2-Pad116)") (class "Default")
      (node (ref "U40") (pin "116") (pinfunction "PD2_116") (pintype "passive"))
    )
    (net (code "103") (name "unconnected-(U40A-PD3-Pad117)") (class "Default")
      (node (ref "U40") (pin "117") (pinfunction "PD3_117") (pintype "passive"))
    )
    (net (code "104") (name "unconnected-(U40A-PD4-Pad118)") (class "Default")
      (node (ref "U40") (pin "118") (pinfunction "PD4_118") (pintype "passive"))
    )
    (net (code "105") (name "unconnected-(U40A-PD7-Pad123)") (class "Default")
      (node (ref "U40") (pin "123") (pinfunction "PD7_123") (pintype "passive"))
    )
    (net (code "106") (name "unconnected-(U40A-PD8-Pad77)") (class "Default")
      (node (ref "U40") (pin "77") (pinfunction "PD8_77") (pintype "passive"))
    )
    (net (code "107") (name "unconnected-(U40A-PD9-Pad78)") (class "Default")
      (node (ref "U40") (pin "78") (pinfunction "PD9_78") (pintype "passive"))
    )
    (net (code "108") (name "unconnected-(U40B-PE7-Pad58)") (class "Default")
      (node (ref "U40") (pin "58") (pinfunction "PE7_58") (pintype "passive"))
    )
    (net (code "109") (name "unconnected-(U40B-PG0-Pad56)") (class "Default")
      (node (ref "U40") (pin "56") (pinfunction "PG0_56") (pintype "passive"))
    )
    (net (code "110") (name "unconnected-(U40B-PG1-Pad57)") (class "Default")
      (node (ref "U40") (pin "57") (pinfunction "PG1_57") (pintype "passive"))
    )
    (net (code "111") (name "unconnected-(U40B-PG2-Pad87)") (class "Default")
      (node (ref "U40") (pin "87") (pinfunction "PG2_87") (pintype "passive"))
    )
    (net (code "112") (name "unconnected-(U40B-PG3-Pad88)") (class "Default")
      (node (ref "U40") (pin "88") (pinfunction "PG3_88") (pintype "passive"))
    )
    (net (code "113") (name "unconnected-(U40B-PG4-Pad89)") (class "Default")
      (node (ref "U40") (pin "89") (pinfunction "PG4_89") (pintype "passive"))
    )
    (net (code "114") (name "unconnected-(U40B-PG5-Pad90)") (class "Default")
      (node (ref "U40") (pin "90") (pinfunction "PG5_90") (pintype "passive"))
    )
    (net (code "115") (name "unconnected-(U40B-PG6-Pad91)") (class "Default")
      (node (ref "U40") (pin "91") (pinfunction "PG6_91") (pintype "passive"))
    )
    (net (code "116") (name "unconnected-(U40B-PG7-Pad92)") (class "Default")
      (node (ref "U40") (pin "92") (pinfunction "PG7_92") (pintype "passive"))
    )
    (net (code "117") (name "unconnected-(U40B-PG8-Pad93)") (class "Default")
      (node (ref "U40") (pin "93") (pinfunction "PG8_93") (pintype "passive"))
    )
    (net (code "118") (name "unconnected-(U40B-PG10-Pad125)") (class "Default")
      (node (ref "U40") (pin "125") (pinfunction "PG10_125") (pintype "passive"))
    )
    (net (code "119") (name "unconnected-(U40B-PG11-Pad126)") (class "Default")
      (node (ref "U40") (pin "126") (pinfunction "PG11_126") (pintype "passive"))
    )
    (net (code "120") (name "unconnected-(U40B-PG12-Pad127)") (class "Default")
      (node (ref "U40") (pin "127") (pinfunction "PG12_127") (pintype "passive"))
    )
    (net (code "121") (name "unconnected-(U40B-PG13-Pad128)") (class "Default")
      (node (ref "U40") (pin "128") (pinfunction "PG13_128") (pintype "passive"))
    )
    (net (code "122") (name "unconnected-(U40B-PG14-Pad129)") (class "Default")
      (node (ref "U40") (pin "129") (pinfunction "PG14_129") (pintype "passive"))
    )
  )
)
